# ADXL335_Breakout.net
KiCad netlist of a schematic drawn in EAGLE
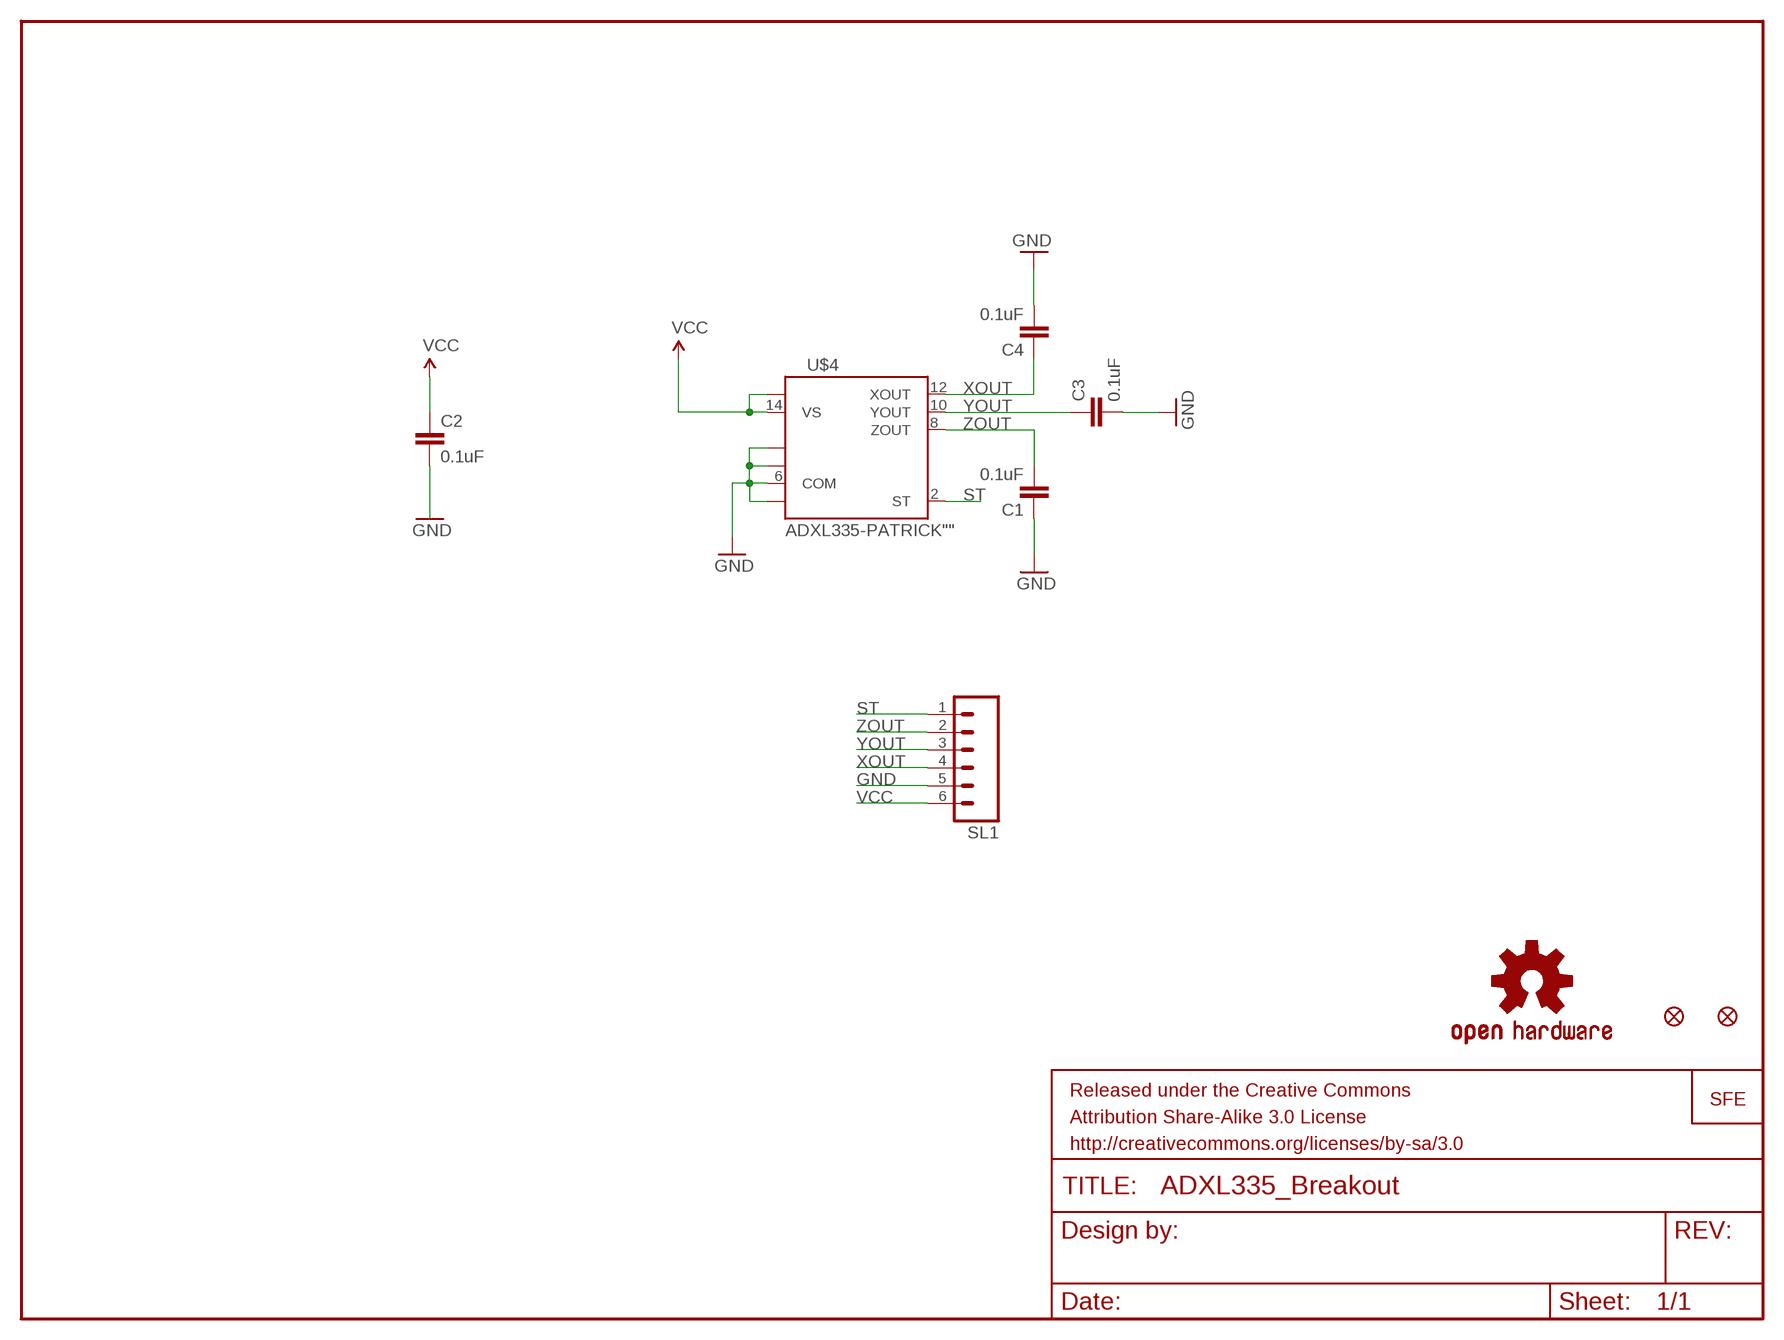
[diagram p0: schematic, sheet 1]

(export (version "E")
  (design (tool "Eeschema 10.0.6"))
  (components
    (comp (ref "C1")
      (value "0.1uF")
      (footprint "eagle-import:0603-CAP")
      (libsource (lib "eagle-import") (part "CAP0603-CAP"))
    )
    (comp (ref "C2")
      (value "0.1uF")
      (footprint "eagle-import:0603-CAP")
      (libsource (lib "eagle-import") (part "CAP0603-CAP"))
    )
    (comp (ref "C3")
      (value "0.1uF")
      (footprint "eagle-import:0603-CAP")
      (libsource (lib "eagle-import") (part "CAP0603-CAP"))
    )
    (comp (ref "C4")
      (value "0.1uF")
      (footprint "eagle-import:0603-CAP")
      (libsource (lib "eagle-import") (part "CAP0603-CAP"))
    )
    (comp (ref "SL1")
      (value "M06SIP")
      (footprint "eagle-import:1X06")
      (libsource (lib "eagle-import") (part "M06SIP"))
    )
    (comp (ref "U$1")
      (value "FIDUCIAL1X2")
      (footprint "eagle-import:FIDUCIAL-1X2")
      (libsource (lib "eagle-import") (part "FIDUCIAL1X2"))
    )
    (comp (ref "U$2")
      (value "LOGO-SFE")
      (footprint "eagle-import:SFE-NEW-WEBLOGO")
      (libsource (lib "eagle-import") (part "LOGO-SFENEW"))
    )
    (comp (ref "U$3")
      (value "FIDUCIAL1X2")
      (footprint "eagle-import:FIDUCIAL-1X2")
      (libsource (lib "eagle-import") (part "FIDUCIAL1X2"))
    )
    (comp (ref "U$4")
      (value "ADXL335-PATRICK\"\"")
      (footprint "eagle-import:ADXL335-P")
      (libsource (lib "eagle-import") (part "ADXL335-PATRICK{dblquote}{dblquote}"))
    )
    (comp (ref "U$5")
      (value "OSHW-LOGOS")
      (footprint "eagle-import:OSHW-LOGO-S")
      (libsource (lib "eagle-import") (part "OSHW-LOGOS"))
    )
  )
  (nets
    (net (code "1") (name "/ST") (class "Default")
      (node (ref "SL1") (pin "1") (pinfunction "1_1") (pintype "passive"))
      (node (ref "U$4") (pin "2") (pinfunction "ST_2") (pintype "bidirectional"))
    )
    (net (code "2") (name "/XOUT") (class "Default")
      (node (ref "C4") (pin "1") (pinfunction "1_1") (pintype "passive"))
      (node (ref "SL1") (pin "4") (pinfunction "4_4") (pintype "passive"))
      (node (ref "U$4") (pin "12") (pinfunction "XOUT_12") (pintype "bidirectional"))
    )
    (net (code "3") (name "/YOUT") (class "Default")
      (node (ref "C3") (pin "1") (pinfunction "1_1") (pintype "passive"))
      (node (ref "SL1") (pin "3") (pinfunction "3_3") (pintype "passive"))
      (node (ref "U$4") (pin "10") (pinfunction "YOUT_10") (pintype "bidirectional"))
    )
    (net (code "4") (name "/ZOUT") (class "Default")
      (node (ref "C1") (pin "2") (pinfunction "2_2") (pintype "passive"))
      (node (ref "SL1") (pin "2") (pinfunction "2_2") (pintype "passive"))
      (node (ref "U$4") (pin "8") (pinfunction "ZOUT_8") (pintype "bidirectional"))
    )
    (net (code "5") (name "GND") (class "Default")
      (node (ref "C1") (pin "1") (pinfunction "1_1") (pintype "passive"))
      (node (ref "C2") (pin "2") (pinfunction "2_2") (pintype "passive"))
      (node (ref "C3") (pin "2") (pinfunction "2_2") (pintype "passive"))
      (node (ref "C4") (pin "2") (pinfunction "2_2") (pintype "passive"))
      (node (ref "SL1") (pin "5") (pinfunction "5_5") (pintype "passive"))
      (node (ref "U$4") (pin "3") (pinfunction "COM_3") (pintype "bidirectional"))
      (node (ref "U$4") (pin "5") (pinfunction "COM_5") (pintype "bidirectional"))
      (node (ref "U$4") (pin "6") (pinfunction "COM_6") (pintype "bidirectional"))
      (node (ref "U$4") (pin "7") (pinfunction "COM_7") (pintype "bidirectional"))
    )
    (net (code "6") (name "VCC") (class "Default")
      (node (ref "C2") (pin "1") (pinfunction "1_1") (pintype "passive"))
      (node (ref "SL1") (pin "6") (pinfunction "6_6") (pintype "passive"))
      (node (ref "U$4") (pin "14") (pinfunction "VS_14") (pintype "bidirectional"))
      (node (ref "U$4") (pin "15") (pinfunction "VS_15") (pintype "bidirectional"))
    )
  )
)
